# PSU.net
KiCad netlist of a schematic drawn in Altium Designer
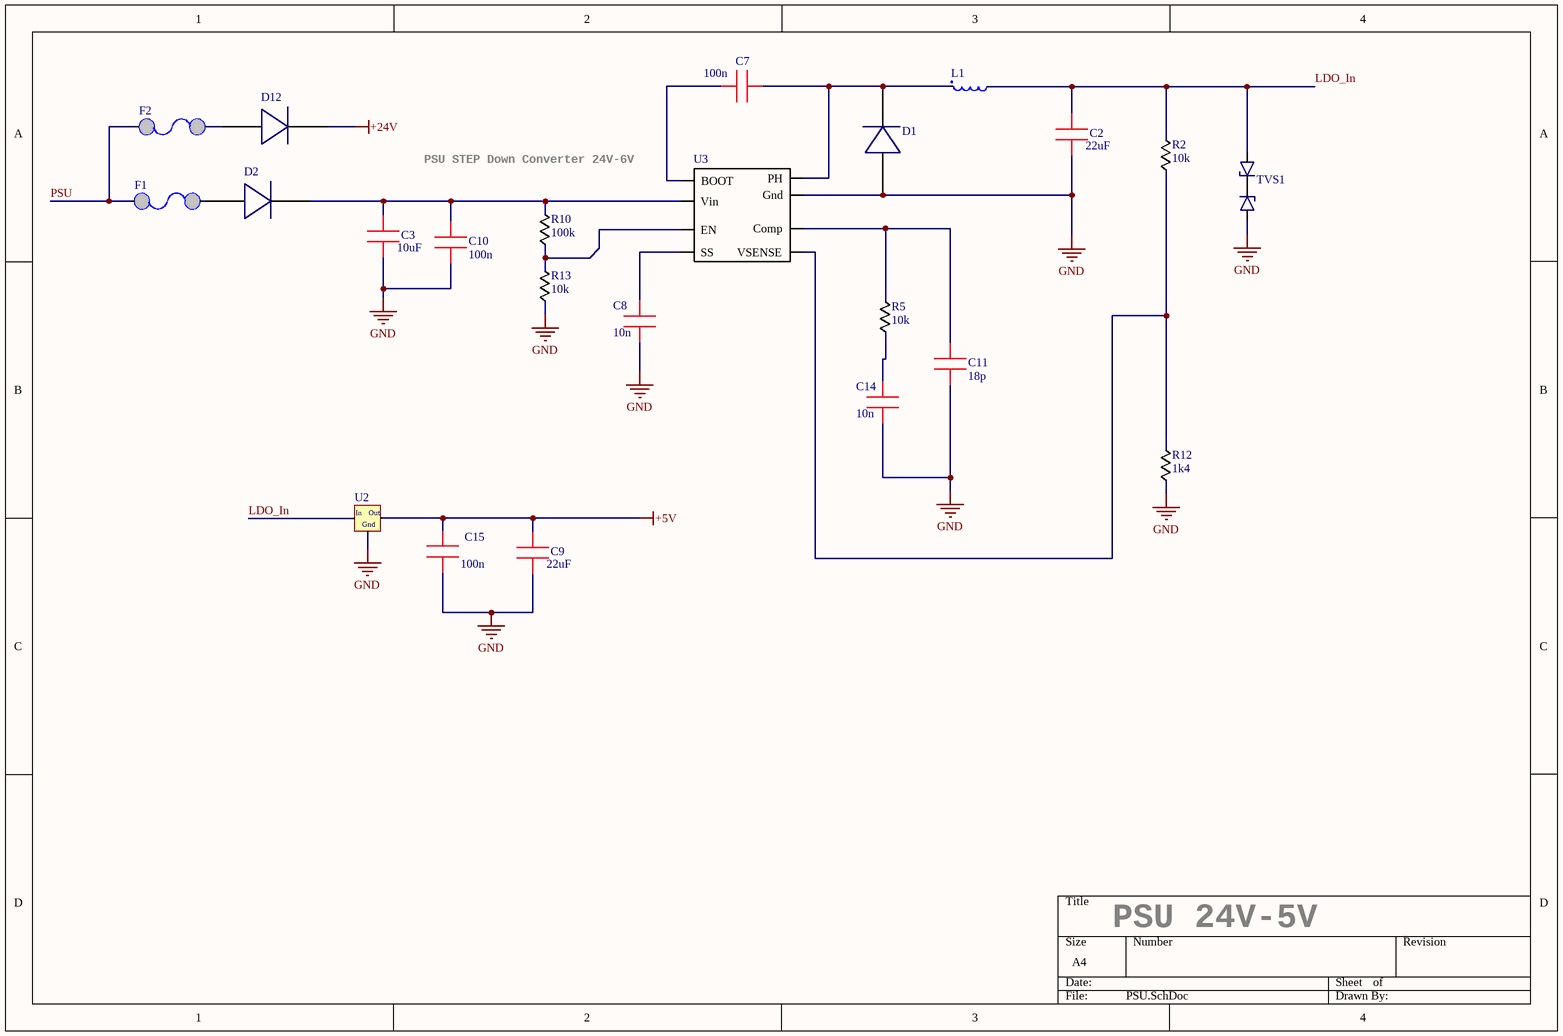
[diagram p0: PSU.SchDoc]

(export (version "E")
  (design (tool "Eeschema 10.0.6"))
  (components
    (comp (ref "C2")
      (value "22uF")
      (footprint "1206_CAP")
      (fields (field (name "PART NUMBER") "CC1206KKX5R7BB226"))
      (libsource (lib "kontr") (part "0805 Cap"))
    )
    (comp (ref "C3")
      (value "10uF")
      (footprint "1206_CAP")
      (fields (field (name "PART NUMBER") "CC1206KKX5R9BB106"))
      (libsource (lib "kontr") (part "0805 Cap"))
    )
    (comp (ref "C7")
      (value "100n")
      (footprint "0603_Cap")
      (fields (field (name "PART NUMBER") "CC0603ZRY5V9BB104"))
      (libsource (lib "kontr") (part "0805 Cap"))
    )
    (comp (ref "C8")
      (value "10n")
      (footprint "0603_Cap")
      (fields (field (name "PART NUMBER") "CC0603ZRY5V9BB103"))
      (libsource (lib "kontr") (part "0805 Cap"))
    )
    (comp (ref "C9")
      (value "22uF")
      (footprint "1206_CAP")
      (fields (field (name "PART NUMBER") "CC1206KKX5R7BB226"))
      (libsource (lib "kontr") (part "0805 Cap"))
    )
    (comp (ref "C10")
      (value "100n")
      (footprint "0603_Cap")
      (fields (field (name "PART NUMBER") "CC0603ZRY5V9BB104"))
      (libsource (lib "kontr") (part "0805 Cap"))
    )
    (comp (ref "C11")
      (value "18p")
      (footprint "0603_Cap")
      (fields (field (name "PART NUMBER") "CC0603JRNPO9BN180"))
      (libsource (lib "kontr") (part "0603 CAP"))
    )
    (comp (ref "C14")
      (value "10n")
      (footprint "0603_Cap")
      (fields (field (name "PART NUMBER") "CC0603ZRY5V9BB103"))
      (libsource (lib "kontr") (part "0805 Cap"))
    )
    (comp (ref "C15")
      (value "100n")
      (footprint "0603_Cap")
      (fields (field (name "PART NUMBER") "CC0603ZRY5V9BB104"))
      (libsource (lib "kontr") (part "Capasitor 0805"))
    )
    (comp (ref "D1")
      (value "~")
      (footprint "B340A-13-F")
      (fields (field (name "PART NUMBER") "B340A-13-F"))
      (libsource (lib "kontr") (part "B340A-13-F"))
    )
    (comp (ref "D2")
      (value "~")
      (footprint "B340A-13-F")
      (fields (field (name "PART NUMBER") "Schottky Diode 40V 3A"))
      (libsource (lib "kontr") (part "B340A-13-F"))
    )
    (comp (ref "D12")
      (value "~")
      (footprint "B340A-13-F")
      (fields (field (name "PART NUMBER") "B340A-13-F"))
      (libsource (lib "kontr") (part "B340A-13-F"))
    )
    (comp (ref "F1")
      (value "~")
      (footprint "Fuse USMF030")
      (fields (field (name "PART NUMBER") "MF-MSMF030-2"))
      (libsource (lib "kontr") (part "Fuse PTS"))
    )
    (comp (ref "F2")
      (value "~")
      (footprint "Fuse USMF030")
      (fields (field (name "PART NUMBER") "MF-MSMF030-2"))
      (libsource (lib "kontr") (part "Fuse PTS"))
    )
    (comp (ref "L1")
      (value "~")
      (footprint "CDRH127/LDNP-270MC,")
      (fields (field (name "PART NUMBER") "CDRH127/LDNP-220MC"))
      (libsource (lib "kontr") (part "CDRH127/LDNP-270MC"))
    )
    (comp (ref "R2")
      (value "10k")
      (footprint "0603_Res")
      (fields (field (name "PART NUMBER") "RT0603FRE0710KL"))
      (libsource (lib "kontr") (part "Resistor 0805"))
    )
    (comp (ref "R5")
      (value "10k")
      (footprint "0603_Res")
      (fields (field (name "PART NUMBER") "RT0603FRE0710KL"))
      (libsource (lib "kontr") (part "Resistor 0805"))
    )
    (comp (ref "R10")
      (value "100k")
      (footprint "0603_Res")
      (fields (field (name "PART NUMBER") "RC0603FR-07100KL"))
      (libsource (lib "kontr") (part "Resistor 0805"))
    )
    (comp (ref "R12")
      (value "1k4")
      (footprint "0603_Res")
      (fields (field (name "PART NUMBER") "RC0603FR-071K4L"))
      (libsource (lib "kontr") (part "Resistor 0805"))
    )
    (comp (ref "R13")
      (value "10k")
      (footprint "0603_Res")
      (fields (field (name "PART NUMBER") "RT0603FRE0710KL"))
      (libsource (lib "kontr") (part "Resistor 0805"))
    )
    (comp (ref "TVS1")
      (value "~")
      (footprint "SM6T")
      (fields (field (name "PART NUMBER") "SM6T12CA"))
      (libsource (lib "kontr") (part "SM6T12CA"))
    )
    (comp (ref "U2")
      (value "~")
      (footprint "SOT223")
      (fields (field (name "PART NUMBER") "LM1117MPX-5.0"))
      (libsource (lib "kontr") (part "NCV1117ST50T3G"))
    )
    (comp (ref "U3")
      (value "~")
      (footprint "SOIC 8")
      (fields (field (name "PART NUMBER") "TPS54331DR"))
      (libsource (lib "kontr") (part "TPS54331"))
    )
  )
  (nets
    (net (code "1") (name "+5V") (class "Default")
      (node (ref "C15") (pin "1") (pinfunction "1_1") (pintype "passive"))
      (node (ref "C9") (pin "2") (pinfunction "2_2") (pintype "passive"))
      (node (ref "U2") (pin "2") (pinfunction "OUT_2") (pintype "passive"))
    )
    (net (code "2") (name "+24V") (class "Default")
      (node (ref "D12") (pin "1") (pinfunction "1_1") (pintype "passive"))
    )
    (net (code "3") (name "/LDO_In") (class "Default")
      (node (ref "C2") (pin "2") (pinfunction "2_2") (pintype "passive"))
      (node (ref "L1") (pin "2") (pinfunction "2_2") (pintype "passive"))
      (node (ref "R2") (pin "2") (pintype "passive"))
      (node (ref "TVS1") (pin "2") (pinfunction "2_2") (pintype "passive"))
      (node (ref "U2") (pin "3") (pinfunction "IN_3") (pintype "passive"))
    )
    (net (code "4") (name "/PSU") (class "Default")
      (node (ref "F1") (pin "1") (pinfunction "1_1") (pintype "passive"))
      (node (ref "F2") (pin "1") (pinfunction "1_1") (pintype "passive"))
    )
    (net (code "5") (name "GND") (class "Default")
      (node (ref "C10") (pin "1") (pinfunction "1_1") (pintype "passive"))
      (node (ref "C11") (pin "1") (pinfunction "1_1") (pintype "passive"))
      (node (ref "C14") (pin "1") (pinfunction "1_1") (pintype "passive"))
      (node (ref "C15") (pin "2") (pinfunction "2_2") (pintype "passive"))
      (node (ref "C2") (pin "1") (pinfunction "1_1") (pintype "passive"))
      (node (ref "C3") (pin "1") (pinfunction "1_1") (pintype "passive"))
      (node (ref "C8") (pin "1") (pinfunction "1_1") (pintype "passive"))
      (node (ref "C9") (pin "1") (pinfunction "1_1") (pintype "passive"))
      (node (ref "D1") (pin "2") (pinfunction "1_2") (pintype "passive"))
      (node (ref "R12") (pin "1") (pintype "passive"))
      (node (ref "R13") (pin "1") (pintype "passive"))
      (node (ref "TVS1") (pin "1") (pinfunction "1_1") (pintype "passive"))
      (node (ref "U2") (pin "1") (pinfunction "GND_1") (pintype "passive"))
      (node (ref "U3") (pin "7") (pinfunction "Gnd_7") (pintype "passive"))
    )
    (net (code "6") (name "Net-(C14-Pad2)") (class "Default")
      (node (ref "C14") (pin "2") (pinfunction "2_2") (pintype "passive"))
      (node (ref "R5") (pin "1") (pintype "passive"))
    )
    (net (code "7") (name "Net-(D2-1-Pad2)") (class "Default")
      (node (ref "D2") (pin "2") (pinfunction "1_2") (pintype "passive"))
      (node (ref "F1") (pin "0") (pinfunction "0_0") (pintype "passive"))
    )
    (net (code "8") (name "Net-(D12-1-Pad2)") (class "Default")
      (node (ref "D12") (pin "2") (pinfunction "1_2") (pintype "passive"))
      (node (ref "F2") (pin "0") (pinfunction "0_0") (pintype "passive"))
    )
    (net (code "9") (name "Net-(U3-BOOT)") (class "Default")
      (node (ref "C7") (pin "1") (pinfunction "1_1") (pintype "passive"))
      (node (ref "U3") (pin "1") (pinfunction "BOOT_1") (pintype "passive"))
    )
    (net (code "10") (name "Net-(U3-Comp)") (class "Default")
      (node (ref "C11") (pin "2") (pinfunction "2_2") (pintype "passive"))
      (node (ref "R5") (pin "2") (pintype "passive"))
      (node (ref "U3") (pin "6") (pinfunction "Comp_6") (pintype "passive"))
    )
    (net (code "11") (name "Net-(U3-EN)") (class "Default")
      (node (ref "R10") (pin "1") (pintype "passive"))
      (node (ref "R13") (pin "2") (pintype "passive"))
      (node (ref "U3") (pin "3") (pinfunction "EN_3") (pintype "passive"))
    )
    (net (code "12") (name "Net-(U3-PH)") (class "Default")
      (node (ref "C7") (pin "2") (pinfunction "2_2") (pintype "passive"))
      (node (ref "D1") (pin "1") (pinfunction "1_1") (pintype "passive"))
      (node (ref "L1") (pin "1") (pinfunction "1_1") (pintype "passive"))
      (node (ref "U3") (pin "8") (pinfunction "PH_8") (pintype "passive"))
    )
    (net (code "13") (name "Net-(U3-SS)") (class "Default")
      (node (ref "C8") (pin "2") (pinfunction "2_2") (pintype "passive"))
      (node (ref "U3") (pin "4") (pinfunction "SS_4") (pintype "passive"))
    )
    (net (code "14") (name "Net-(U3-VSENSE)") (class "Default")
      (node (ref "R12") (pin "2") (pintype "passive"))
      (node (ref "R2") (pin "1") (pintype "passive"))
      (node (ref "U3") (pin "5") (pinfunction "VSENSE_5") (pintype "passive"))
    )
    (net (code "15") (name "Net-(U3-Vin)") (class "Default")
      (node (ref "C10") (pin "2") (pinfunction "2_2") (pintype "passive"))
      (node (ref "C3") (pin "2") (pinfunction "2_2") (pintype "passive"))
      (node (ref "D2") (pin "1") (pinfunction "1_1") (pintype "passive"))
      (node (ref "R10") (pin "2") (pintype "passive"))
      (node (ref "U3") (pin "2") (pinfunction "Vin_2") (pintype "passive"))
    )
  )
)
